# Sense_7_Signal_Isolation.net
KiCad netlist of a schematic drawn in Altium Designer
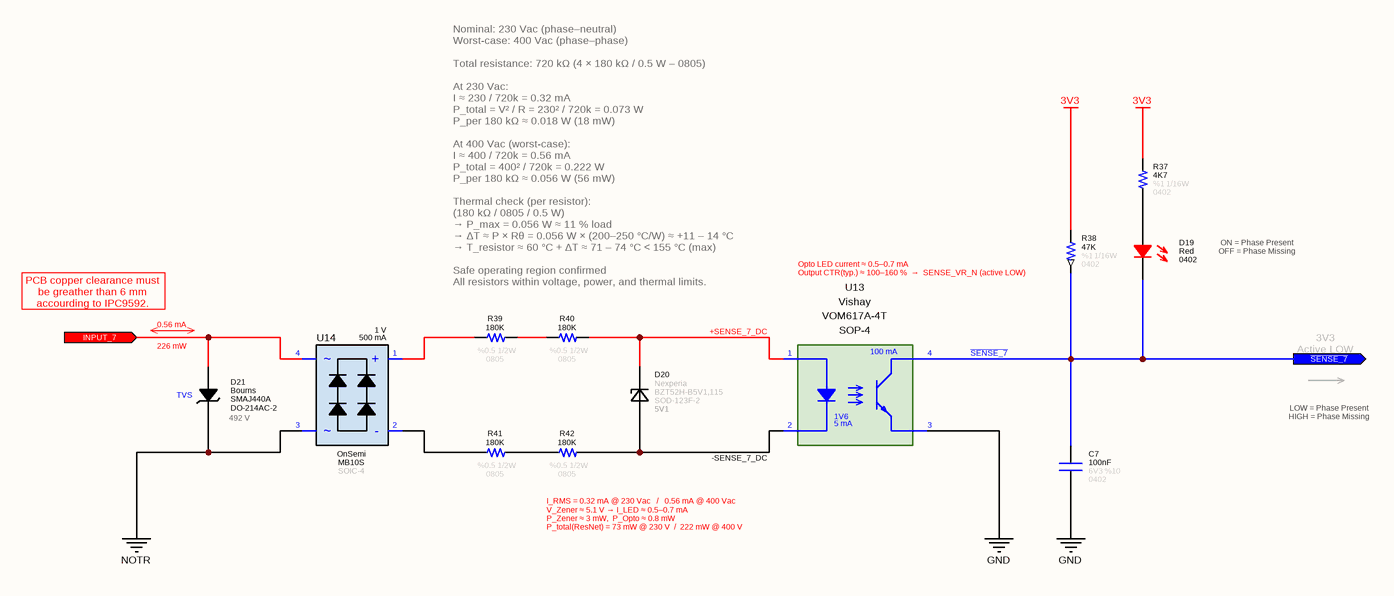
[diagram p0: Sense 7 Signal Isolation.SchDoc]

(export (version "E")
  (design (tool "Eeschema 10.0.6"))
  (components
    (comp (ref "C7")
      (value "100nF")
      (footprint "CAPACITOR_0402")
      (description "Capacitor (MLCC) - 100nF / 6V3 / 0402")
      (fields
        (field (name "MANUFACTURER PART NUMBER") "04026D104KAT4A")
        (field (name "TOLERANCE") "%10")
        (field (name "VOLTAGE") "6V3")
        (field (name "CASE") "0402")
        (field (name "Comment") "Capacitor - 100nF [0402] (MLCC)")
      )
      (libsource (lib "Akkoyun") (part "Capacitor - 100nF [0402-6V3]"))
    )
    (comp (ref "D19")
      (value "SMD LED (Red)")
      (footprint "LED_0402")
      (description "Standard LEDs - SMD MINI-MOLD ULTRA COMPACT RED")
      (fields
        (field (name "MANUFACTURER PART NUMBER") "SML-P12VTT86R")
        (field (name "CASE") "0402")
        (field (name "COLOR") "Red")
      )
      (libsource (lib "Akkoyun") (part "Diode - LED (0402-Red)"))
    )
    (comp (ref "D20")
      (value "BZT52H-B5V1,115")
      (footprint "SOD-123F-2")
      (description "Zener Diodes BZT52H-B5V1/SOD123F/SOD2")
      (fields
        (field (name "ZENER VOLTAGE") "5V1")
        (field (name "MANUFACTURER NAME") "Nexperia")
        (field (name "MANUFACTURER PART NUMBER") "BZT52H-B5V1,115")
        (field (name "CASE") "SOD-123F-2")
      )
      (libsource (lib "Akkoyun") (part "Diode - BZT52H-B5V1,115"))
    )
    (comp (ref "D21")
      (value "SMAJ440A")
      (footprint "DO-220AA-2")
      (description "ESD Protection Diodes / TVS Diodes 440volts 1uA .6 Amps Uni-Dir")
      (fields
        (field (name "BREAKDOWN VOLTAGE") "492 V")
        (field (name "MANUFACTURER NAME") "Bourns")
        (field (name "MANUFACTURER PART NUMBER") "SMAJ440A")
        (field (name "CASE") "DO-214AC-2")
      )
      (libsource (lib "Akkoyun") (part "Diode - SMAJ440A (TVS)"))
    )
    (comp (ref "R37")
      (value "4K7")
      (footprint "RESISTOR_0402")
      (description "Thick Film Resistors - SMD 1/16 W 4.7 KOhm 1%")
      (fields
        (field (name "MANUFACTURER PART NUMBER") "CRCW04024K70FKED")
        (field (name "TOLERANCE") "%1")
        (field (name "CASE") "0402")
        (field (name "POWER") "1/16W")
        (field (name "Comment") "4K7 - 0402 - %1 - 1/16W")
      )
      (libsource (lib "Akkoyun") (part "Resistor - 4K7 [0402]"))
    )
    (comp (ref "R38")
      (value "47K")
      (footprint "RESISTOR_0402")
      (description "Thick Film Resistors - SMD 1/16 W 47 KOhm 1%")
      (fields
        (field (name "MANUFACTURER PART NUMBER") "CRCW040247K0FKED")
        (field (name "TOLERANCE") "%1")
        (field (name "CASE") "0402")
        (field (name "POWER") "1/16W")
        (field (name "Comment") "47K - 0402 - %1 - 1/16W")
      )
      (libsource (lib "Akkoyun") (part "Resistor - 47K [0402]"))
    )
    (comp (ref "R39")
      (value "180K")
      (footprint "RESISTOR_0805")
      (description "Thick Film Resistors - SMD 0805 180Kohms 0.5W 0.5% AEC-Q200")
      (fields
        (field (name "MANUFACTURER PART NUMBER") "ERJ-P06D1803V")
        (field (name "TOLERANCE") "%0.5")
        (field (name "CASE") "0805")
        (field (name "POWER") "1/2W")
        (field (name "Comment") "180K - 0805 - %0.5 - 1/2W")
      )
      (libsource (lib "Akkoyun") (part "Resistor - 180K [0805]"))
    )
    (comp (ref "R40")
      (value "180K")
      (footprint "RESISTOR_0805")
      (description "Thick Film Resistors - SMD 0805 180Kohms 0.5W 0.5% AEC-Q200")
      (fields
        (field (name "MANUFACTURER PART NUMBER") "ERJ-P06D1803V")
        (field (name "TOLERANCE") "%0.5")
        (field (name "CASE") "0805")
        (field (name "POWER") "1/2W")
        (field (name "Comment") "180K - 0805 - %0.5 - 1/2W")
      )
      (libsource (lib "Akkoyun") (part "Resistor - 180K [0805]"))
    )
    (comp (ref "R41")
      (value "180K")
      (footprint "RESISTOR_0805")
      (description "Thick Film Resistors - SMD 0805 180Kohms 0.5W 0.5% AEC-Q200")
      (fields
        (field (name "MANUFACTURER PART NUMBER") "ERJ-P06D1803V")
        (field (name "TOLERANCE") "%0.5")
        (field (name "CASE") "0805")
        (field (name "POWER") "1/2W")
        (field (name "Comment") "180K - 0805 - %0.5 - 1/2W")
      )
      (libsource (lib "Akkoyun") (part "Resistor - 180K [0805]"))
    )
    (comp (ref "R42")
      (value "180K")
      (footprint "RESISTOR_0805")
      (description "Thick Film Resistors - SMD 0805 180Kohms 0.5W 0.5% AEC-Q200")
      (fields
        (field (name "MANUFACTURER PART NUMBER") "ERJ-P06D1803V")
        (field (name "TOLERANCE") "%0.5")
        (field (name "CASE") "0805")
        (field (name "POWER") "1/2W")
        (field (name "Comment") "180K - 0805 - %0.5 - 1/2W")
      )
      (libsource (lib "Akkoyun") (part "Resistor - 180K [0805]"))
    )
    (comp (ref "U13")
      (value "VOM617A-4T")
      (footprint "SOP-4V2")
      (description "Transistor Output Optocouplers Phototransistor Out CTR 160-320% 5mA")
      (fields
        (field (name "MANUFACTURER PART NUMBER") "VOM617A-4T")
        (field (name "MANUFACTURER NAME") "Vishay")
        (field (name "CASE") "SOP-4")
        (field (name "IF - FORWARD CURRENT") "5 mA")
        (field (name "VF - FORWARD VOLTAGE") "1V6")
        (field (name "MAXIMUM COLLECTOR CURRENT") "100 mA")
      )
      (libsource (lib "Akkoyun") (part "IC - VOM617A"))
    )
    (comp (ref "U14")
      (value "LTV-846S")
      (footprint "SOIC-4")
      (description "Transistor Output Optocouplers Optocplr Phototrans 4-Channel")
      (fields
        (field (name "IF - FORWARD CURRENT") "500 mA")
        (field (name "VF - FORWARD VOLTAGE") "1 V")
        (field (name "MANUFACTURER NAME") "OnSemi")
        (field (name "MANUFACTURER PART NUMBER") "MB10S")
        (field (name "CASE") "SOIC-4")
      )
      (libsource (lib "Akkoyun") (part "IC - MB10S"))
    )
  )
  (nets
    (net (code "1") (name "/+SENSE_7_DC") (class "Default")
      (node (ref "D20") (pin "1") (pinfunction "Cathode_1") (pintype "passive"))
      (node (ref "R40") (pin "1") (pinfunction "1_1") (pintype "passive"))
      (node (ref "U13") (pin "1") (pinfunction "LED_Anode_1") (pintype "passive"))
    )
    (net (code "2") (name "/-SENSE_7_DC") (class "Default")
      (node (ref "D20") (pin "2") (pinfunction "Anode_2") (pintype "passive"))
      (node (ref "R42") (pin "1") (pinfunction "1_1") (pintype "passive"))
      (node (ref "U13") (pin "2") (pinfunction "LED_Cathode_2") (pintype "passive"))
    )
    (net (code "3") (name "/INPUT_7") (class "Default")
      (node (ref "D21") (pin "1") (pinfunction "Anode_1") (pintype "passive"))
      (node (ref "U14") (pin "4") (pinfunction "~_4") (pintype "passive"))
    )
    (net (code "4") (name "/~{SENSE_7}") (class "Default")
      (node (ref "C7") (pin "2") (pinfunction "2_2") (pintype "passive"))
      (node (ref "D19") (pin "1") (pinfunction "1_1") (pintype "passive"))
      (node (ref "R38") (pin "1") (pinfunction "1_1") (pintype "output"))
      (node (ref "U13") (pin "4") (pinfunction "Collector_4") (pintype "passive"))
    )
    (net (code "5") (name "3V3") (class "Default")
      (node (ref "R37") (pin "2") (pinfunction "2_2") (pintype "passive"))
      (node (ref "R38") (pin "2") (pinfunction "2_2") (pintype "passive"))
    )
    (net (code "6") (name "GND") (class "Default")
      (node (ref "C7") (pin "1") (pinfunction "1_1") (pintype "passive"))
      (node (ref "U13") (pin "3") (pinfunction "Emiter_3") (pintype "passive"))
    )
    (net (code "7") (name "NOTR") (class "Default")
      (node (ref "D21") (pin "2") (pinfunction "Cathode_2") (pintype "passive"))
      (node (ref "U14") (pin "3") (pinfunction "~_3") (pintype "passive"))
    )
    (net (code "8") (name "Net-(D19-Pad2)") (class "Default")
      (node (ref "D19") (pin "2") (pinfunction "2_2") (pintype "passive"))
      (node (ref "R37") (pin "1") (pinfunction "1_1") (pintype "passive"))
    )
    (net (code "9") (name "Net-(R39-Pad1)") (class "Default")
      (node (ref "R39") (pin "1") (pinfunction "1_1") (pintype "passive"))
      (node (ref "R40") (pin "2") (pinfunction "2_2") (pintype "passive"))
    )
    (net (code "10") (name "Net-(R41-Pad1)") (class "Default")
      (node (ref "R41") (pin "1") (pinfunction "1_1") (pintype "passive"))
      (node (ref "R42") (pin "2") (pinfunction "2_2") (pintype "passive"))
    )
    (net (code "11") (name "Net-(U14-+)") (class "Default")
      (node (ref "R39") (pin "2") (pinfunction "2_2") (pintype "passive"))
      (node (ref "U14") (pin "1") (pinfunction "+_1") (pintype "passive"))
    )
    (net (code "12") (name "Net-(U14--)") (class "Default")
      (node (ref "R41") (pin "2") (pinfunction "2_2") (pintype "passive"))
      (node (ref "U14") (pin "2") (pinfunction "-_2") (pintype "passive"))
    )
  )
)
